# 14KEY.net
KiCad netlist of a schematic drawn in EAGLE
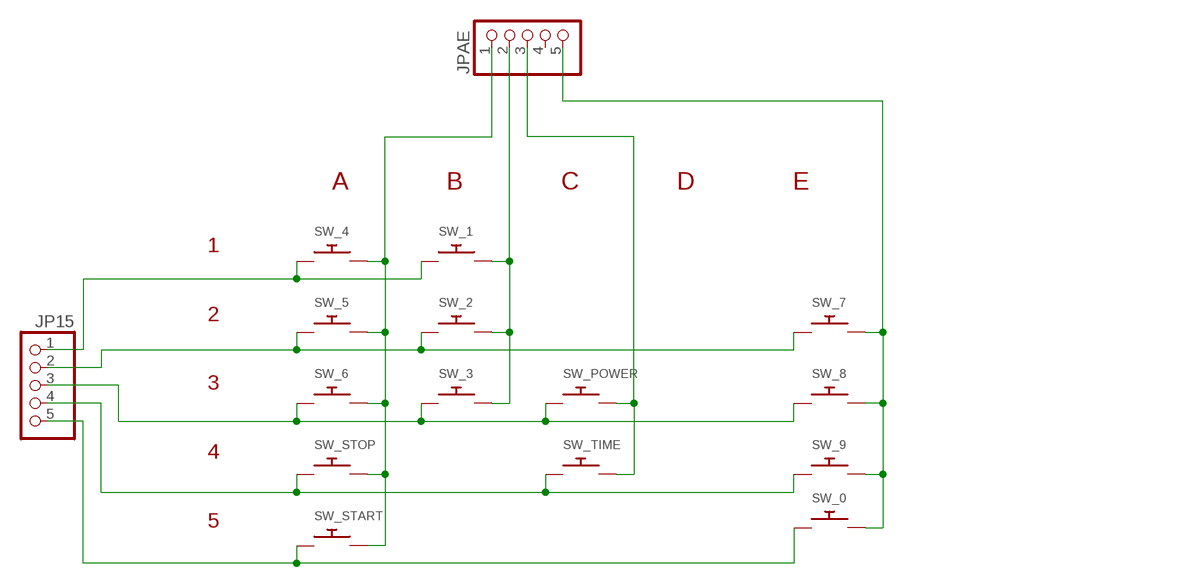
[diagram p0: schematic, sheet 1]

(export (version "E")
  (design (tool "Eeschema 10.0.6"))
  (components
    (comp (ref "JP15")
      (value "PINHD-1X5")
      (footprint "eagle-import:1X05")
      (libsource (lib "eagle-import") (part "PINHD-1X5"))
    )
    (comp (ref "JPAE")
      (value "PINHD-1X5")
      (footprint "eagle-import:1X05")
      (libsource (lib "eagle-import") (part "PINHD-1X5"))
    )
    (comp (ref "SW_0")
      (value "SWITCH_PUSHBUTTONEVQ-PE")
      (footprint "eagle-import:TACT_PANA-EVQ")
      (libsource (lib "eagle-import") (part "SWITCH_PUSHBUTTONEVQ-PE"))
    )
    (comp (ref "SW_1")
      (value "SWITCH_PUSHBUTTONEVQ-PE")
      (footprint "eagle-import:TACT_PANA-EVQ")
      (libsource (lib "eagle-import") (part "SWITCH_PUSHBUTTONEVQ-PE"))
    )
    (comp (ref "SW_2")
      (value "SWITCH_PUSHBUTTONEVQ-PE")
      (footprint "eagle-import:TACT_PANA-EVQ")
      (libsource (lib "eagle-import") (part "SWITCH_PUSHBUTTONEVQ-PE"))
    )
    (comp (ref "SW_3")
      (value "SWITCH_PUSHBUTTONEVQ-PE")
      (footprint "eagle-import:TACT_PANA-EVQ")
      (libsource (lib "eagle-import") (part "SWITCH_PUSHBUTTONEVQ-PE"))
    )
    (comp (ref "SW_4")
      (value "SWITCH_PUSHBUTTONEVQ-PE")
      (footprint "eagle-import:TACT_PANA-EVQ")
      (libsource (lib "eagle-import") (part "SWITCH_PUSHBUTTONEVQ-PE"))
    )
    (comp (ref "SW_5")
      (value "SWITCH_PUSHBUTTONEVQ-PE")
      (footprint "eagle-import:TACT_PANA-EVQ")
      (libsource (lib "eagle-import") (part "SWITCH_PUSHBUTTONEVQ-PE"))
    )
    (comp (ref "SW_6")
      (value "SWITCH_PUSHBUTTONEVQ-PE")
      (footprint "eagle-import:TACT_PANA-EVQ")
      (libsource (lib "eagle-import") (part "SWITCH_PUSHBUTTONEVQ-PE"))
    )
    (comp (ref "SW_7")
      (value "SWITCH_PUSHBUTTONEVQ-PE")
      (footprint "eagle-import:TACT_PANA-EVQ")
      (libsource (lib "eagle-import") (part "SWITCH_PUSHBUTTONEVQ-PE"))
    )
    (comp (ref "SW_8")
      (value "SWITCH_PUSHBUTTONEVQ-PE")
      (footprint "eagle-import:TACT_PANA-EVQ")
      (libsource (lib "eagle-import") (part "SWITCH_PUSHBUTTONEVQ-PE"))
    )
    (comp (ref "SW_9")
      (value "SWITCH_PUSHBUTTONEVQ-PE")
      (footprint "eagle-import:TACT_PANA-EVQ")
      (libsource (lib "eagle-import") (part "SWITCH_PUSHBUTTONEVQ-PE"))
    )
    (comp (ref "SW_POWER")
      (value "SWITCH_PUSHBUTTONEVQ-PE")
      (footprint "eagle-import:TACT_PANA-EVQ")
      (libsource (lib "eagle-import") (part "SWITCH_PUSHBUTTONEVQ-PE"))
    )
    (comp (ref "SW_START")
      (value "SWITCH_PUSHBUTTONEVQ-PE")
      (footprint "eagle-import:TACT_PANA-EVQ")
      (libsource (lib "eagle-import") (part "SWITCH_PUSHBUTTONEVQ-PE"))
    )
    (comp (ref "SW_STOP")
      (value "SWITCH_PUSHBUTTONEVQ-PE")
      (footprint "eagle-import:TACT_PANA-EVQ")
      (libsource (lib "eagle-import") (part "SWITCH_PUSHBUTTONEVQ-PE"))
    )
    (comp (ref "SW_TIME")
      (value "SWITCH_PUSHBUTTONEVQ-PE")
      (footprint "eagle-import:TACT_PANA-EVQ")
      (libsource (lib "eagle-import") (part "SWITCH_PUSHBUTTONEVQ-PE"))
    )
  )
  (nets
    (net (code "1") (name "Net-(JP15-Pad1)") (class "Default")
      (node (ref "JP15") (pin "1") (pinfunction "1_1") (pintype "passive"))
      (node (ref "SW_1") (pin "P$1") (pinfunction "P$1_P$1") (pintype "passive"))
      (node (ref "SW_4") (pin "P$1") (pinfunction "P$1_P$1") (pintype "passive"))
    )
    (net (code "2") (name "Net-(JP15-Pad2)") (class "Default")
      (node (ref "JP15") (pin "2") (pinfunction "2_2") (pintype "passive"))
      (node (ref "SW_2") (pin "P$1") (pinfunction "P$1_P$1") (pintype "passive"))
      (node (ref "SW_5") (pin "P$1") (pinfunction "P$1_P$1") (pintype "passive"))
      (node (ref "SW_7") (pin "P$1") (pinfunction "P$1_P$1") (pintype "passive"))
    )
    (net (code "3") (name "Net-(JP15-Pad3)") (class "Default")
      (node (ref "JP15") (pin "3") (pinfunction "3_3") (pintype "passive"))
      (node (ref "SW_3") (pin "P$1") (pinfunction "P$1_P$1") (pintype "passive"))
      (node (ref "SW_6") (pin "P$1") (pinfunction "P$1_P$1") (pintype "passive"))
      (node (ref "SW_8") (pin "P$1") (pinfunction "P$1_P$1") (pintype "passive"))
      (node (ref "SW_POWER") (pin "P$1") (pinfunction "P$1_P$1") (pintype "passive"))
    )
    (net (code "4") (name "Net-(JP15-Pad4)") (class "Default")
      (node (ref "JP15") (pin "4") (pinfunction "4_4") (pintype "passive"))
      (node (ref "SW_9") (pin "P$1") (pinfunction "P$1_P$1") (pintype "passive"))
      (node (ref "SW_STOP") (pin "P$1") (pinfunction "P$1_P$1") (pintype "passive"))
      (node (ref "SW_TIME") (pin "P$1") (pinfunction "P$1_P$1") (pintype "passive"))
    )
    (net (code "5") (name "Net-(JP15-Pad5)") (class "Default")
      (node (ref "JP15") (pin "5") (pinfunction "5_5") (pintype "passive"))
      (node (ref "SW_0") (pin "P$1") (pinfunction "P$1_P$1") (pintype "passive"))
      (node (ref "SW_START") (pin "P$1") (pinfunction "P$1_P$1") (pintype "passive"))
    )
    (net (code "6") (name "Net-(JPAE-Pad1)") (class "Default")
      (node (ref "JPAE") (pin "1") (pinfunction "1_1") (pintype "passive"))
      (node (ref "SW_4") (pin "P$2") (pinfunction "P$2_P$2") (pintype "passive"))
      (node (ref "SW_5") (pin "P$2") (pinfunction "P$2_P$2") (pintype "passive"))
      (node (ref "SW_6") (pin "P$2") (pinfunction "P$2_P$2") (pintype "passive"))
      (node (ref "SW_START") (pin "P$2") (pinfunction "P$2_P$2") (pintype "passive"))
      (node (ref "SW_STOP") (pin "P$2") (pinfunction "P$2_P$2") (pintype "passive"))
    )
    (net (code "7") (name "Net-(JPAE-Pad2)") (class "Default")
      (node (ref "JPAE") (pin "2") (pinfunction "2_2") (pintype "passive"))
      (node (ref "SW_1") (pin "P$2") (pinfunction "P$2_P$2") (pintype "passive"))
      (node (ref "SW_2") (pin "P$2") (pinfunction "P$2_P$2") (pintype "passive"))
      (node (ref "SW_3") (pin "P$2") (pinfunction "P$2_P$2") (pintype "passive"))
    )
    (net (code "8") (name "Net-(JPAE-Pad3)") (class "Default")
      (node (ref "JPAE") (pin "3") (pinfunction "3_3") (pintype "passive"))
      (node (ref "SW_POWER") (pin "P$2") (pinfunction "P$2_P$2") (pintype "passive"))
      (node (ref "SW_TIME") (pin "P$2") (pinfunction "P$2_P$2") (pintype "passive"))
    )
    (net (code "9") (name "Net-(JPAE-Pad5)") (class "Default")
      (node (ref "JPAE") (pin "5") (pinfunction "5_5") (pintype "passive"))
      (node (ref "SW_0") (pin "P$2") (pinfunction "P$2_P$2") (pintype "passive"))
      (node (ref "SW_7") (pin "P$2") (pinfunction "P$2_P$2") (pintype "passive"))
      (node (ref "SW_8") (pin "P$2") (pinfunction "P$2_P$2") (pintype "passive"))
      (node (ref "SW_9") (pin "P$2") (pinfunction "P$2_P$2") (pintype "passive"))
    )
    (net (code "10") (name "unconnected-(JPAE-Pad4)") (class "Default")
      (node (ref "JPAE") (pin "4") (pinfunction "4_4") (pintype "passive"))
    )
  )
)
